# Simon_Says_Jump_MAIN.net
KiCad netlist of a schematic drawn in EAGLE
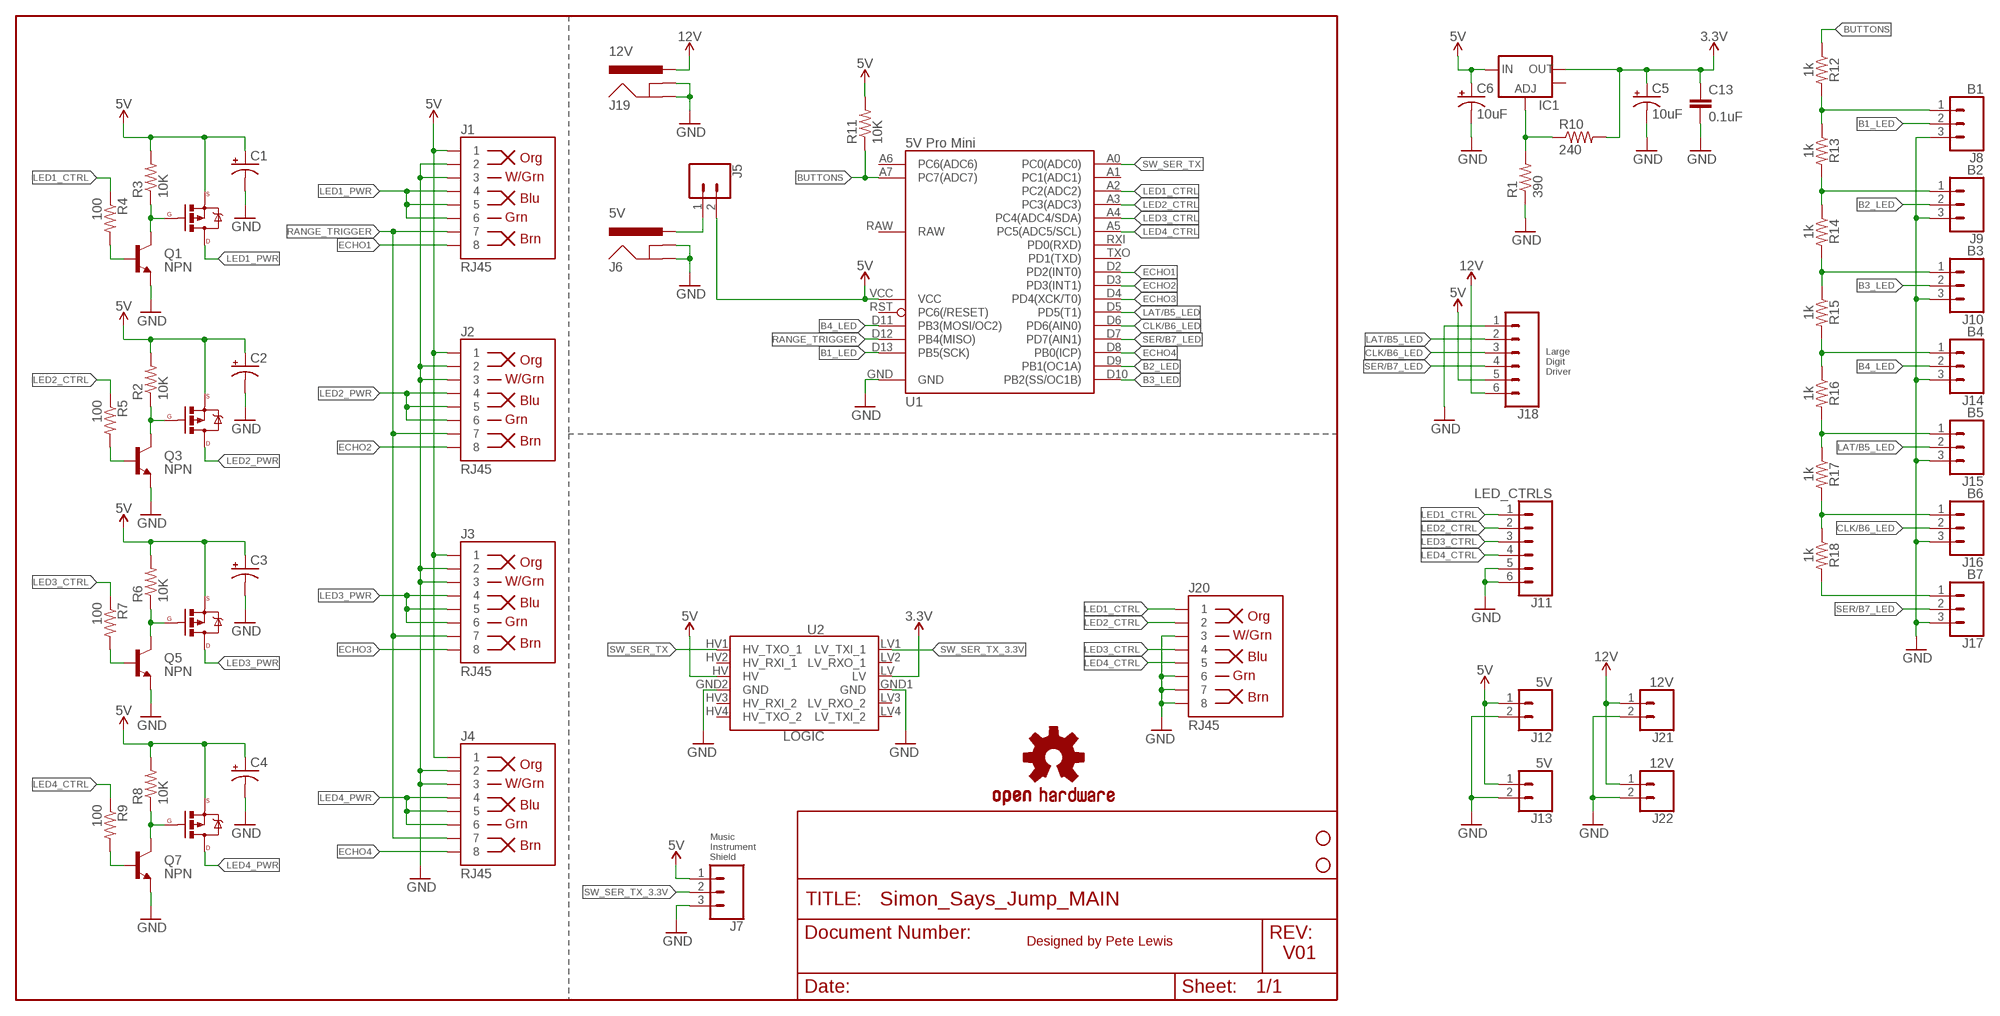
[diagram p0: schematic, sheet 1]

(export (version "E")
  (design (tool "Eeschema 10.0.6"))
  (components
    (comp (ref "C1")
      (value "CAP_POLCPOL-RADIAL-10UF-25V-KIT")
      (footprint "eagle-import:CPOL-RADIAL-10UF-25V-KIT")
      (libsource (lib "eagle-import") (part "CAP_POLCPOL-RADIAL-10UF-25V-KIT"))
    )
    (comp (ref "C2")
      (value "CAP_POLCPOL-RADIAL-10UF-25V-KIT")
      (footprint "eagle-import:CPOL-RADIAL-10UF-25V-KIT")
      (libsource (lib "eagle-import") (part "CAP_POLCPOL-RADIAL-10UF-25V-KIT"))
    )
    (comp (ref "C3")
      (value "CAP_POLCPOL-RADIAL-10UF-25V-KIT")
      (footprint "eagle-import:CPOL-RADIAL-10UF-25V-KIT")
      (libsource (lib "eagle-import") (part "CAP_POLCPOL-RADIAL-10UF-25V-KIT"))
    )
    (comp (ref "C4")
      (value "CAP_POLCPOL-RADIAL-10UF-25V-KIT")
      (footprint "eagle-import:CPOL-RADIAL-10UF-25V-KIT")
      (libsource (lib "eagle-import") (part "CAP_POLCPOL-RADIAL-10UF-25V-KIT"))
    )
    (comp (ref "C5")
      (value "10uF")
      (footprint "eagle-import:EIA3216")
      (libsource (lib "eagle-import") (part "CAP_POL1206"))
    )
    (comp (ref "C6")
      (value "10uF")
      (footprint "eagle-import:EIA3216")
      (libsource (lib "eagle-import") (part "CAP_POL1206"))
    )
    (comp (ref "C13")
      (value "0.1uF")
      (footprint "eagle-import:0603-CAP")
      (libsource (lib "eagle-import") (part "CAP0603-CAP"))
    )
    (comp (ref "IC1")
      (value "V_REG_LM1117SOT223")
      (footprint "eagle-import:SOT223")
      (libsource (lib "eagle-import") (part "V_REG_LM1117SOT223"))
    )
    (comp (ref "J1")
      (value "RJ45")
      (footprint "eagle-import:RJ45-8")
      (libsource (lib "eagle-import") (part "RJ45-8"))
    )
    (comp (ref "J2")
      (value "RJ45")
      (footprint "eagle-import:RJ45-8")
      (libsource (lib "eagle-import") (part "RJ45-8"))
    )
    (comp (ref "J3")
      (value "RJ45")
      (footprint "eagle-import:RJ45-8")
      (libsource (lib "eagle-import") (part "RJ45-8"))
    )
    (comp (ref "J4")
      (value "RJ45")
      (footprint "eagle-import:RJ45-8")
      (libsource (lib "eagle-import") (part "RJ45-8"))
    )
    (comp (ref "J5")
      (value "CONN_02PTH3")
      (footprint "eagle-import:1X02_LONGPADS")
      (libsource (lib "eagle-import") (part "CONN_02PTH3"))
    )
    (comp (ref "J6")
      (value "5V")
      (footprint "eagle-import:POWER_JACK_PTH_LOCK")
      (libsource (lib "eagle-import") (part "POWER_JACKPTH_LOCK"))
    )
    (comp (ref "J7")
      (value "CONN_03LONGPADS")
      (footprint "eagle-import:1X03_LONGPADS")
      (libsource (lib "eagle-import") (part "CONN_03LONGPADS"))
    )
    (comp (ref "J8")
      (value "B1")
      (footprint "eagle-import:1X03_LONGPADS")
      (libsource (lib "eagle-import") (part "CONN_03LONGPADS"))
    )
    (comp (ref "J9")
      (value "B2")
      (footprint "eagle-import:1X03_LONGPADS")
      (libsource (lib "eagle-import") (part "CONN_03LONGPADS"))
    )
    (comp (ref "J10")
      (value "B3")
      (footprint "eagle-import:1X03_LONGPADS")
      (libsource (lib "eagle-import") (part "CONN_03LONGPADS"))
    )
    (comp (ref "J11")
      (value "LED_CTRLS")
      (footprint "eagle-import:1X06_LONGPADS")
      (libsource (lib "eagle-import") (part "CONN_06LONGPADS"))
    )
    (comp (ref "J12")
      (value "5V")
      (footprint "eagle-import:1X02_LONGPADS")
      (libsource (lib "eagle-import") (part "CONN_02PTH3"))
    )
    (comp (ref "J13")
      (value "5V")
      (footprint "eagle-import:1X02_LONGPADS")
      (libsource (lib "eagle-import") (part "CONN_02PTH3"))
    )
    (comp (ref "J14")
      (value "B4")
      (footprint "eagle-import:1X03_LONGPADS")
      (libsource (lib "eagle-import") (part "CONN_03LONGPADS"))
    )
    (comp (ref "J15")
      (value "B5")
      (footprint "eagle-import:1X03_LONGPADS")
      (libsource (lib "eagle-import") (part "CONN_03LONGPADS"))
    )
    (comp (ref "J16")
      (value "B6")
      (footprint "eagle-import:1X03_LONGPADS")
      (libsource (lib "eagle-import") (part "CONN_03LONGPADS"))
    )
    (comp (ref "J17")
      (value "B7")
      (footprint "eagle-import:1X03_LONGPADS")
      (libsource (lib "eagle-import") (part "CONN_03LONGPADS"))
    )
    (comp (ref "J18")
      (value "CONN_06LONGPADS")
      (footprint "eagle-import:1X06_LONGPADS")
      (libsource (lib "eagle-import") (part "CONN_06LONGPADS"))
    )
    (comp (ref "J19")
      (value "12V")
      (footprint "eagle-import:POWER_JACK_PTH_LOCK")
      (libsource (lib "eagle-import") (part "POWER_JACKPTH_LOCK"))
    )
    (comp (ref "J20")
      (value "RJ45")
      (footprint "eagle-import:RJ45-8")
      (libsource (lib "eagle-import") (part "RJ45-8"))
    )
    (comp (ref "J21")
      (value "12V")
      (footprint "eagle-import:1X02_LONGPADS")
      (libsource (lib "eagle-import") (part "CONN_02PTH3"))
    )
    (comp (ref "J22")
      (value "12V")
      (footprint "eagle-import:1X02_LONGPADS")
      (libsource (lib "eagle-import") (part "CONN_02PTH3"))
    )
    (comp (ref "JP1")
      (value "STAND-OFFTIGHTER")
      (footprint "eagle-import:STAND-OFF-TIGHTER")
      (libsource (lib "eagle-import") (part "STAND-OFFTIGHTER"))
    )
    (comp (ref "JP7")
      (value "STAND-OFFTIGHTER")
      (footprint "eagle-import:STAND-OFF-TIGHTER")
      (libsource (lib "eagle-import") (part "STAND-OFFTIGHTER"))
    )
    (comp (ref "LOGO1")
      (value "OSHW-LOGOL")
      (footprint "eagle-import:OSHW-LOGO-L")
      (libsource (lib "eagle-import") (part "OSHW-LOGOL"))
    )
    (comp (ref "Q1")
      (value "NPN")
      (footprint "eagle-import:SOT23")
      (libsource (lib "eagle-import") (part "TRANSISTOR_NPNSOT23"))
    )
    (comp (ref "Q2")
      (value "P-Channel MOSFET")
      (footprint "eagle-import:TO220V")
      (libsource (lib "eagle-import") (part "MOSFET-PCHANNELPTH"))
    )
    (comp (ref "Q3")
      (value "NPN")
      (footprint "eagle-import:SOT23")
      (libsource (lib "eagle-import") (part "TRANSISTOR_NPNSOT23"))
    )
    (comp (ref "Q4")
      (value "P-Channel MOSFET")
      (footprint "eagle-import:TO220V")
      (libsource (lib "eagle-import") (part "MOSFET-PCHANNELPTH"))
    )
    (comp (ref "Q5")
      (value "NPN")
      (footprint "eagle-import:SOT23")
      (libsource (lib "eagle-import") (part "TRANSISTOR_NPNSOT23"))
    )
    (comp (ref "Q6")
      (value "P-Channel MOSFET")
      (footprint "eagle-import:TO220V")
      (libsource (lib "eagle-import") (part "MOSFET-PCHANNELPTH"))
    )
    (comp (ref "Q7")
      (value "NPN")
      (footprint "eagle-import:SOT23")
      (libsource (lib "eagle-import") (part "TRANSISTOR_NPNSOT23"))
    )
    (comp (ref "Q8")
      (value "P-Channel MOSFET")
      (footprint "eagle-import:TO220V")
      (libsource (lib "eagle-import") (part "MOSFET-PCHANNELPTH"))
    )
    (comp (ref "R1")
      (value "390")
      (footprint "eagle-import:0603-RES")
      (libsource (lib "eagle-import") (part "RESISTOR0603-RES"))
    )
    (comp (ref "R2")
      (value "10K")
      (footprint "eagle-import:0603-RES")
      (libsource (lib "eagle-import") (part "RESISTOR0603-RES"))
    )
    (comp (ref "R3")
      (value "10K")
      (footprint "eagle-import:0603-RES")
      (libsource (lib "eagle-import") (part "RESISTOR0603-RES"))
    )
    (comp (ref "R4")
      (value "100")
      (footprint "eagle-import:0603-RES")
      (libsource (lib "eagle-import") (part "RESISTOR0603-RES"))
    )
    (comp (ref "R5")
      (value "100")
      (footprint "eagle-import:0603-RES")
      (libsource (lib "eagle-import") (part "RESISTOR0603-RES"))
    )
    (comp (ref "R6")
      (value "10K")
      (footprint "eagle-import:0603-RES")
      (libsource (lib "eagle-import") (part "RESISTOR0603-RES"))
    )
    (comp (ref "R7")
      (value "100")
      (footprint "eagle-import:0603-RES")
      (libsource (lib "eagle-import") (part "RESISTOR0603-RES"))
    )
    (comp (ref "R8")
      (value "10K")
      (footprint "eagle-import:0603-RES")
      (libsource (lib "eagle-import") (part "RESISTOR0603-RES"))
    )
    (comp (ref "R9")
      (value "100")
      (footprint "eagle-import:0603-RES")
      (libsource (lib "eagle-import") (part "RESISTOR0603-RES"))
    )
    (comp (ref "R10")
      (value "240")
      (footprint "eagle-import:0603-RES")
      (libsource (lib "eagle-import") (part "RESISTOR0603-RES"))
    )
    (comp (ref "R11")
      (value "10K")
      (footprint "eagle-import:0603-RES")
      (libsource (lib "eagle-import") (part "RESISTOR0603-RES"))
    )
    (comp (ref "R12")
      (value "1k")
      (footprint "eagle-import:0603")
      (libsource (lib "eagle-import") (part "1KOHM-0603-1/10W-1%"))
    )
    (comp (ref "R13")
      (value "1k")
      (footprint "eagle-import:0603")
      (libsource (lib "eagle-import") (part "1KOHM-0603-1/10W-1%"))
    )
    (comp (ref "R14")
      (value "1k")
      (footprint "eagle-import:0603")
      (libsource (lib "eagle-import") (part "1KOHM-0603-1/10W-1%"))
    )
    (comp (ref "R15")
      (value "1k")
      (footprint "eagle-import:0603")
      (libsource (lib "eagle-import") (part "1KOHM-0603-1/10W-1%"))
    )
    (comp (ref "R16")
      (value "1k")
      (footprint "eagle-import:0603")
      (libsource (lib "eagle-import") (part "1KOHM-0603-1/10W-1%"))
    )
    (comp (ref "R17")
      (value "1k")
      (footprint "eagle-import:0603")
      (libsource (lib "eagle-import") (part "1KOHM-0603-1/10W-1%"))
    )
    (comp (ref "R18")
      (value "1k")
      (footprint "eagle-import:0603")
      (libsource (lib "eagle-import") (part "1KOHM-0603-1/10W-1%"))
    )
    (comp (ref "U1")
      (value "5V Pro Mini")
      (footprint "eagle-import:ARDUINO_PRO_MINI-V13_DIP")
      (libsource (lib "eagle-import") (part "ARDUINO_PRO_MINI-V13-DIP"))
    )
    (comp (ref "U2")
      (value "LOGIC")
      (footprint "eagle-import:SPARKFUN_LOGIC_LEVEL_CONVERTER")
      (libsource (lib "eagle-import") (part "SPARKFUN_LOGIC_LEVEL_CONVERTER"))
    )
  )
  (nets
    (net (code "1") (name "3.3V") (class "Default")
      (node (ref "C13") (pin "1") (pinfunction "1_1") (pintype "passive"))
      (node (ref "C5") (pin "A") (pinfunction "+_A") (pintype "passive"))
      (node (ref "IC1") (pin "2") (pinfunction "OUT_2") (pintype "output"))
      (node (ref "R10") (pin "2") (pinfunction "2_2") (pintype "passive"))
      (node (ref "U2") (pin "LV") (pinfunction "LV_LV") (pintype "power_in"))
    )
    (net (code "2") (name "5V") (class "Default")
      (node (ref "C1") (pin "1") (pinfunction "+_1") (pintype "passive"))
      (node (ref "C2") (pin "1") (pinfunction "+_1") (pintype "passive"))
      (node (ref "C3") (pin "1") (pinfunction "+_1") (pintype "passive"))
      (node (ref "C4") (pin "1") (pinfunction "+_1") (pintype "passive"))
      (node (ref "C6") (pin "A") (pinfunction "+_A") (pintype "passive"))
      (node (ref "IC1") (pin "3") (pinfunction "IN_3") (pintype "input"))
      (node (ref "J1") (pin "1") (pinfunction "1_1") (pintype "bidirectional"))
      (node (ref "J12") (pin "1") (pinfunction "1_1") (pintype "passive"))
      (node (ref "J13") (pin "1") (pinfunction "1_1") (pintype "passive"))
      (node (ref "J18") (pin "5") (pinfunction "5_5") (pintype "passive"))
      (node (ref "J2") (pin "1") (pinfunction "1_1") (pintype "bidirectional"))
      (node (ref "J3") (pin "1") (pinfunction "1_1") (pintype "bidirectional"))
      (node (ref "J4") (pin "1") (pinfunction "1_1") (pintype "bidirectional"))
      (node (ref "J5") (pin "2") (pinfunction "2_2") (pintype "passive"))
      (node (ref "J7") (pin "1") (pinfunction "1_1") (pintype "passive"))
      (node (ref "Q2") (pin "3") (pinfunction "S_3") (pintype "passive"))
      (node (ref "Q4") (pin "3") (pinfunction "S_3") (pintype "passive"))
      (node (ref "Q6") (pin "3") (pinfunction "S_3") (pintype "passive"))
      (node (ref "Q8") (pin "3") (pinfunction "S_3") (pintype "passive"))
      (node (ref "R11") (pin "2") (pinfunction "2_2") (pintype "passive"))
      (node (ref "R2") (pin "2") (pinfunction "2_2") (pintype "passive"))
      (node (ref "R3") (pin "2") (pinfunction "2_2") (pintype "passive"))
      (node (ref "R6") (pin "2") (pinfunction "2_2") (pintype "passive"))
      (node (ref "R8") (pin "2") (pinfunction "2_2") (pintype "passive"))
      (node (ref "U1") (pin "VCC") (pinfunction "VCC_VCC") (pintype "bidirectional"))
      (node (ref "U2") (pin "HV") (pinfunction "HV_HV") (pintype "power_in"))
    )
    (net (code "3") (name "12V") (class "Default")
      (node (ref "J18") (pin "6") (pinfunction "6_6") (pintype "passive"))
      (node (ref "J19") (pin "PWR") (pinfunction "PWR_PWR") (pintype "bidirectional"))
      (node (ref "J21") (pin "1") (pinfunction "1_1") (pintype "passive"))
      (node (ref "J22") (pin "1") (pinfunction "1_1") (pintype "passive"))
    )
    (net (code "4") (name "B1_LED") (class "Default")
      (node (ref "J8") (pin "2") (pinfunction "2_2") (pintype "passive"))
      (node (ref "U1") (pin "D13") (pinfunction "PB5(SCK)_D13") (pintype "bidirectional"))
    )
    (net (code "5") (name "B2_LED") (class "Default")
      (node (ref "J9") (pin "2") (pinfunction "2_2") (pintype "passive"))
      (node (ref "U1") (pin "D9") (pinfunction "PB1(OC1A)_D9") (pintype "bidirectional"))
    )
    (net (code "6") (name "B3_LED") (class "Default")
      (node (ref "J10") (pin "2") (pinfunction "2_2") (pintype "passive"))
      (node (ref "U1") (pin "D10") (pinfunction "PB2(SS/OC1B)_D10") (pintype "bidirectional"))
    )
    (net (code "7") (name "B4_LED") (class "Default")
      (node (ref "J14") (pin "2") (pinfunction "2_2") (pintype "passive"))
      (node (ref "U1") (pin "D11") (pinfunction "PB3(MOSI/OC2)_D11") (pintype "bidirectional"))
    )
    (net (code "8") (name "BUTTONS") (class "Default")
      (node (ref "R11") (pin "1") (pinfunction "1_1") (pintype "passive"))
      (node (ref "R12") (pin "1") (pinfunction "1_1") (pintype "passive"))
      (node (ref "U1") (pin "A7") (pinfunction "PC7(ADC7)_A7") (pintype "bidirectional"))
    )
    (net (code "9") (name "CLK{slash}B6_LED") (class "Default")
      (node (ref "J16") (pin "2") (pinfunction "2_2") (pintype "passive"))
      (node (ref "J18") (pin "3") (pinfunction "3_3") (pintype "passive"))
      (node (ref "U1") (pin "D6") (pinfunction "PD6(AIN0)_D6") (pintype "bidirectional"))
    )
    (net (code "10") (name "ECHO1") (class "Default")
      (node (ref "J1") (pin "8") (pinfunction "8_8") (pintype "bidirectional"))
      (node (ref "U1") (pin "D2") (pinfunction "PD2(INT0)_D2") (pintype "bidirectional"))
    )
    (net (code "11") (name "ECHO2") (class "Default")
      (node (ref "J2") (pin "8") (pinfunction "8_8") (pintype "bidirectional"))
      (node (ref "U1") (pin "D3") (pinfunction "PD3(INT1)_D3") (pintype "bidirectional"))
    )
    (net (code "12") (name "ECHO3") (class "Default")
      (node (ref "J3") (pin "8") (pinfunction "8_8") (pintype "bidirectional"))
      (node (ref "U1") (pin "D4") (pinfunction "PD4(XCK/T0)_D4") (pintype "bidirectional"))
    )
    (net (code "13") (name "ECHO4") (class "Default")
      (node (ref "J4") (pin "8") (pinfunction "8_8") (pintype "bidirectional"))
      (node (ref "U1") (pin "D8") (pinfunction "PB0(ICP)_D8") (pintype "bidirectional"))
    )
    (net (code "14") (name "GND") (class "Default")
      (node (ref "C1") (pin "2") (pinfunction "-_2") (pintype "passive"))
      (node (ref "C13") (pin "2") (pinfunction "2_2") (pintype "passive"))
      (node (ref "C2") (pin "2") (pinfunction "-_2") (pintype "passive"))
      (node (ref "C3") (pin "2") (pinfunction "-_2") (pintype "passive"))
      (node (ref "C4") (pin "2") (pinfunction "-_2") (pintype "passive"))
      (node (ref "C5") (pin "C") (pinfunction "-_C") (pintype "passive"))
      (node (ref "C6") (pin "C") (pinfunction "-_C") (pintype "passive"))
      (node (ref "J1") (pin "2") (pinfunction "2_2") (pintype "bidirectional"))
      (node (ref "J1") (pin "3") (pinfunction "3_3") (pintype "bidirectional"))
      (node (ref "J10") (pin "3") (pinfunction "3_3") (pintype "passive"))
      (node (ref "J11") (pin "5") (pinfunction "5_5") (pintype "passive"))
      (node (ref "J11") (pin "6") (pinfunction "6_6") (pintype "passive"))
      (node (ref "J12") (pin "2") (pinfunction "2_2") (pintype "passive"))
      (node (ref "J13") (pin "2") (pinfunction "2_2") (pintype "passive"))
      (node (ref "J14") (pin "3") (pinfunction "3_3") (pintype "passive"))
      (node (ref "J15") (pin "3") (pinfunction "3_3") (pintype "passive"))
      (node (ref "J16") (pin "3") (pinfunction "3_3") (pintype "passive"))
      (node (ref "J17") (pin "3") (pinfunction "3_3") (pintype "passive"))
      (node (ref "J18") (pin "1") (pinfunction "1_1") (pintype "passive"))
      (node (ref "J19") (pin "GND") (pinfunction "GND_GND") (pintype "bidirectional"))
      (node (ref "J19") (pin "GNDBREAK") (pinfunction "GNDBREAK_GNDBREAK") (pintype "bidirectional"))
      (node (ref "J2") (pin "2") (pinfunction "2_2") (pintype "bidirectional"))
      (node (ref "J2") (pin "3") (pinfunction "3_3") (pintype "bidirectional"))
      (node (ref "J20") (pin "3") (pinfunction "3_3") (pintype "bidirectional"))
      (node (ref "J20") (pin "6") (pinfunction "6_6") (pintype "bidirectional"))
      (node (ref "J20") (pin "7") (pinfunction "7_7") (pintype "bidirectional"))
      (node (ref "J20") (pin "8") (pinfunction "8_8") (pintype "bidirectional"))
      (node (ref "J21") (pin "2") (pinfunction "2_2") (pintype "passive"))
      (node (ref "J22") (pin "2") (pinfunction "2_2") (pintype "passive"))
      (node (ref "J3") (pin "2") (pinfunction "2_2") (pintype "bidirectional"))
      (node (ref "J3") (pin "3") (pinfunction "3_3") (pintype "bidirectional"))
      (node (ref "J4") (pin "2") (pinfunction "2_2") (pintype "bidirectional"))
      (node (ref "J4") (pin "3") (pinfunction "3_3") (pintype "bidirectional"))
      (node (ref "J6") (pin "GND") (pinfunction "GND_GND") (pintype "bidirectional"))
      (node (ref "J6") (pin "GNDBREAK") (pinfunction "GNDBREAK_GNDBREAK") (pintype "bidirectional"))
      (node (ref "J7") (pin "3") (pinfunction "3_3") (pintype "passive"))
      (node (ref "J8") (pin "3") (pinfunction "3_3") (pintype "passive"))
      (node (ref "J9") (pin "3") (pinfunction "3_3") (pintype "passive"))
      (node (ref "Q1") (pin "2") (pinfunction "E_2") (pintype "passive"))
      (node (ref "Q3") (pin "2") (pinfunction "E_2") (pintype "passive"))
      (node (ref "Q5") (pin "2") (pinfunction "E_2") (pintype "passive"))
      (node (ref "Q7") (pin "2") (pinfunction "E_2") (pintype "passive"))
      (node (ref "R1") (pin "1") (pinfunction "1_1") (pintype "passive"))
      (node (ref "U1") (pin "GND") (pinfunction "GND_GND") (pintype "bidirectional"))
      (node (ref "U2") (pin "GND1") (pinfunction "GND_GND1") (pintype "power_in"))
      (node (ref "U2") (pin "GND2") (pinfunction "GND_GND2") (pintype "power_in"))
    )
    (net (code "15") (name "LAT{slash}B5_LED") (class "Default")
      (node (ref "J15") (pin "2") (pinfunction "2_2") (pintype "passive"))
      (node (ref "J18") (pin "2") (pinfunction "2_2") (pintype "passive"))
      (node (ref "U1") (pin "D5") (pinfunction "PD5(T1)_D5") (pintype "bidirectional"))
    )
    (net (code "16") (name "LED1_CTRL") (class "Default")
      (node (ref "J11") (pin "1") (pinfunction "1_1") (pintype "passive"))
      (node (ref "J20") (pin "1") (pinfunction "1_1") (pintype "bidirectional"))
      (node (ref "R4") (pin "1") (pinfunction "1_1") (pintype "passive"))
      (node (ref "U1") (pin "A2") (pinfunction "PC2(ADC2)_A2") (pintype "bidirectional"))
    )
    (net (code "17") (name "LED1_PWR") (class "Default")
      (node (ref "J1") (pin "4") (pinfunction "4_4") (pintype "bidirectional"))
      (node (ref "J1") (pin "5") (pinfunction "5_5") (pintype "bidirectional"))
      (node (ref "J1") (pin "6") (pinfunction "6_6") (pintype "bidirectional"))
      (node (ref "Q2") (pin "2") (pinfunction "D_2") (pintype "passive"))
    )
    (net (code "18") (name "LED2_CTRL") (class "Default")
      (node (ref "J11") (pin "2") (pinfunction "2_2") (pintype "passive"))
      (node (ref "J20") (pin "2") (pinfunction "2_2") (pintype "bidirectional"))
      (node (ref "R5") (pin "1") (pinfunction "1_1") (pintype "passive"))
      (node (ref "U1") (pin "A3") (pinfunction "PC3(ADC3)_A3") (pintype "bidirectional"))
    )
    (net (code "19") (name "LED2_PWR") (class "Default")
      (node (ref "J2") (pin "4") (pinfunction "4_4") (pintype "bidirectional"))
      (node (ref "J2") (pin "5") (pinfunction "5_5") (pintype "bidirectional"))
      (node (ref "J2") (pin "6") (pinfunction "6_6") (pintype "bidirectional"))
      (node (ref "Q4") (pin "2") (pinfunction "D_2") (pintype "passive"))
    )
    (net (code "20") (name "LED3_CTRL") (class "Default")
      (node (ref "J11") (pin "3") (pinfunction "3_3") (pintype "passive"))
      (node (ref "J20") (pin "4") (pinfunction "4_4") (pintype "bidirectional"))
      (node (ref "R7") (pin "1") (pinfunction "1_1") (pintype "passive"))
      (node (ref "U1") (pin "A4") (pinfunction "PC4(ADC4/SDA)_A4") (pintype "bidirectional"))
    )
    (net (code "21") (name "LED3_PWR") (class "Default")
      (node (ref "J3") (pin "4") (pinfunction "4_4") (pintype "bidirectional"))
      (node (ref "J3") (pin "5") (pinfunction "5_5") (pintype "bidirectional"))
      (node (ref "J3") (pin "6") (pinfunction "6_6") (pintype "bidirectional"))
      (node (ref "Q6") (pin "2") (pinfunction "D_2") (pintype "passive"))
    )
    (net (code "22") (name "LED4_CTRL") (class "Default")
      (node (ref "J11") (pin "4") (pinfunction "4_4") (pintype "passive"))
      (node (ref "J20") (pin "5") (pinfunction "5_5") (pintype "bidirectional"))
      (node (ref "R9") (pin "1") (pinfunction "1_1") (pintype "passive"))
      (node (ref "U1") (pin "A5") (pinfunction "PC5(ADC5/SCL)_A5") (pintype "bidirectional"))
    )
    (net (code "23") (name "LED4_PWR") (class "Default")
      (node (ref "J4") (pin "4") (pinfunction "4_4") (pintype "bidirectional"))
      (node (ref "J4") (pin "5") (pinfunction "5_5") (pintype "bidirectional"))
      (node (ref "J4") (pin "6") (pinfunction "6_6") (pintype "bidirectional"))
      (node (ref "Q8") (pin "2") (pinfunction "D_2") (pintype "passive"))
    )
    (net (code "24") (name "Net-(IC1-ADJ)") (class "Default")
      (node (ref "IC1") (pin "1") (pinfunction "ADJ_1") (pintype "input"))
      (node (ref "R1") (pin "2") (pinfunction "2_2") (pintype "passive"))
      (node (ref "R10") (pin "1") (pinfunction "1_1") (pintype "passive"))
    )
    (net (code "25") (name "Net-(J5-Pad1)") (class "Default")
      (node (ref "J5") (pin "1") (pinfunction "1_1") (pintype "passive"))
      (node (ref "J6") (pin "PWR") (pinfunction "PWR_PWR") (pintype "bidirectional"))
    )
    (net (code "26") (name "Net-(J8-Pad1)") (class "Default")
      (node (ref "J8") (pin "1") (pinfunction "1_1") (pintype "passive"))
      (node (ref "R12") (pin "2") (pinfunction "2_2") (pintype "passive"))
      (node (ref "R13") (pin "1") (pinfunction "1_1") (pintype "passive"))
    )
    (net (code "27") (name "Net-(J9-Pad1)") (class "Default")
      (node (ref "J9") (pin "1") (pinfunction "1_1") (pintype "passive"))
      (node (ref "R13") (pin "2") (pinfunction "2_2") (pintype "passive"))
      (node (ref "R14") (pin "1") (pinfunction "1_1") (pintype "passive"))
    )
    (net (code "28") (name "Net-(J10-Pad1)") (class "Default")
      (node (ref "J10") (pin "1") (pinfunction "1_1") (pintype "passive"))
      (node (ref "R14") (pin "2") (pinfunction "2_2") (pintype "passive"))
      (node (ref "R15") (pin "1") (pinfunction "1_1") (pintype "passive"))
    )
    (net (code "29") (name "Net-(J14-Pad1)") (class "Default")
      (node (ref "J14") (pin "1") (pinfunction "1_1") (pintype "passive"))
      (node (ref "R15") (pin "2") (pinfunction "2_2") (pintype "passive"))
      (node (ref "R16") (pin "1") (pinfunction "1_1") (pintype "passive"))
    )
    (net (code "30") (name "Net-(J15-Pad1)") (class "Default")
      (node (ref "J15") (pin "1") (pinfunction "1_1") (pintype "passive"))
      (node (ref "R16") (pin "2") (pinfunction "2_2") (pintype "passive"))
      (node (ref "R17") (pin "1") (pinfunction "1_1") (pintype "passive"))
    )
    (net (code "31") (name "Net-(J16-Pad1)") (class "Default")
      (node (ref "J16") (pin "1") (pinfunction "1_1") (pintype "passive"))
      (node (ref "R17") (pin "2") (pinfunction "2_2") (pintype "passive"))
      (node (ref "R18") (pin "1") (pinfunction "1_1") (pintype "passive"))
    )
    (net (code "32") (name "Net-(J17-Pad1)") (class "Default")
      (node (ref "J17") (pin "1") (pinfunction "1_1") (pintype "passive"))
      (node (ref "R18") (pin "2") (pinfunction "2_2") (pintype "passive"))
    )
    (net (code "33") (name "Net-(Q1-B)") (class "Default")
      (node (ref "Q1") (pin "1") (pinfunction "B_1") (pintype "passive"))
      (node (ref "R4") (pin "2") (pinfunction "2_2") (pintype "passive"))
    )
    (net (code "34") (name "Net-(Q1-C)") (class "Default")
      (node (ref "Q1") (pin "3") (pinfunction "C_3") (pintype "passive"))
      (node (ref "Q2") (pin "1") (pinfunction "G_1") (pintype "passive"))
      (node (ref "R3") (pin "1") (pinfunction "1_1") (pintype "passive"))
    )
    (net (code "35") (name "Net-(Q3-B)") (class "Default")
      (node (ref "Q3") (pin "1") (pinfunction "B_1") (pintype "passive"))
      (node (ref "R5") (pin "2") (pinfunction "2_2") (pintype "passive"))
    )
    (net (code "36") (name "Net-(Q3-C)") (class "Default")
      (node (ref "Q3") (pin "3") (pinfunction "C_3") (pintype "passive"))
      (node (ref "Q4") (pin "1") (pinfunction "G_1") (pintype "passive"))
      (node (ref "R2") (pin "1") (pinfunction "1_1") (pintype "passive"))
    )
    (net (code "37") (name "Net-(Q5-B)") (class "Default")
      (node (ref "Q5") (pin "1") (pinfunction "B_1") (pintype "passive"))
      (node (ref "R7") (pin "2") (pinfunction "2_2") (pintype "passive"))
    )
    (net (code "38") (name "Net-(Q5-C)") (class "Default")
      (node (ref "Q5") (pin "3") (pinfunction "C_3") (pintype "passive"))
      (node (ref "Q6") (pin "1") (pinfunction "G_1") (pintype "passive"))
      (node (ref "R6") (pin "1") (pinfunction "1_1") (pintype "passive"))
    )
    (net (code "39") (name "Net-(Q7-B)") (class "Default")
      (node (ref "Q7") (pin "1") (pinfunction "B_1") (pintype "passive"))
      (node (ref "R9") (pin "2") (pinfunction "2_2") (pintype "passive"))
    )
    (net (code "40") (name "Net-(Q7-C)") (class "Default")
      (node (ref "Q7") (pin "3") (pinfunction "C_3") (pintype "passive"))
      (node (ref "Q8") (pin "1") (pinfunction "G_1") (pintype "passive"))
      (node (ref "R8") (pin "1") (pinfunction "1_1") (pintype "passive"))
    )
    (net (code "41") (name "RANGE_TRIGGER") (class "Default")
      (node (ref "J1") (pin "7") (pinfunction "7_7") (pintype "bidirectional"))
      (node (ref "J2") (pin "7") (pinfunction "7_7") (pintype "bidirectional"))
      (node (ref "J3") (pin "7") (pinfunction "7_7") (pintype "bidirectional"))
      (node (ref "J4") (pin "7") (pinfunction "7_7") (pintype "bidirectional"))
      (node (ref "U1") (pin "D12") (pinfunction "PB4(MISO)_D12") (pintype "bidirectional"))
    )
    (net (code "42") (name "SER{slash}B7_LED") (class "Default")
      (node (ref "J17") (pin "2") (pinfunction "2_2") (pintype "passive"))
      (node (ref "J18") (pin "4") (pinfunction "4_4") (pintype "passive"))
      (node (ref "U1") (pin "D7") (pinfunction "PD7(AIN1)_D7") (pintype "bidirectional"))
    )
    (net (code "43") (name "SW_SER_TX") (class "Default")
      (node (ref "U1") (pin "A0") (pinfunction "PC0(ADC0)_A0") (pintype "bidirectional"))
      (node (ref "U2") (pin "HV1") (pinfunction "HV_TXO_1_HV1") (pintype "bidirectional"))
    )
    (net (code "44") (name "SW_SER_TX_3.3V") (class "Default")
      (node (ref "J7") (pin "2") (pinfunction "2_2") (pintype "passive"))
      (node (ref "U2") (pin "LV1") (pinfunction "LV_TXI_1_LV1") (pintype "bidirectional"))
    )
    (net (code "45") (name "unconnected-(IC1-OUT-Pad4)") (class "Default")
      (node (ref "IC1") (pin "4") (pinfunction "OUT_4") (pintype "output"))
    )
    (net (code "46") (name "unconnected-(U1-PC1(ADC1)-PadA1)") (class "Default")
      (node (ref "U1") (pin "A1") (pinfunction "PC1(ADC1)_A1") (pintype "bidirectional"))
    )
    (net (code "47") (name "unconnected-(U1-PC6(ADC6)-PadA6)") (class "Default")
      (node (ref "U1") (pin "A6") (pinfunction "PC6(ADC6)_A6") (pintype "bidirectional"))
    )
    (net (code "48") (name "unconnected-(U1-PC6({slash}RESET)-PadRST)") (class "Default")
      (node (ref "U1") (pin "RST") (pinfunction "PC6(/RESET)_RST") (pintype "bidirectional"))
    )
    (net (code "49") (name "unconnected-(U1-PD0(RXD)-PadRXI)") (class "Default")
      (node (ref "U1") (pin "RXI") (pinfunction "PD0(RXD)_RXI") (pintype "bidirectional"))
    )
    (net (code "50") (name "unconnected-(U1-PD1(TXD)-PadTXO)") (class "Default")
      (node (ref "U1") (pin "TXO") (pinfunction "PD1(TXD)_TXO") (pintype "bidirectional"))
    )
    (net (code "51") (name "unconnected-(U1-PadRAW)") (class "Default")
      (node (ref "U1") (pin "RAW") (pinfunction "RAW_RAW") (pintype "bidirectional"))
    )
    (net (code "52") (name "unconnected-(U2-HV_RXI_1-PadHV2)") (class "Default")
      (node (ref "U2") (pin "HV2") (pinfunction "HV_RXI_1_HV2") (pintype "bidirectional"))
    )
    (net (code "53") (name "unconnected-(U2-HV_RXI_2-PadHV3)") (class "Default")
      (node (ref "U2") (pin "HV3") (pinfunction "HV_RXI_2_HV3") (pintype "bidirectional"))
    )
    (net (code "54") (name "unconnected-(U2-HV_TXO_2-PadHV4)") (class "Default")
      (node (ref "U2") (pin "HV4") (pinfunction "HV_TXO_2_HV4") (pintype "bidirectional"))
    )
    (net (code "55") (name "unconnected-(U2-LV_RXO_1-PadLV2)") (class "Default")
      (node (ref "U2") (pin "LV2") (pinfunction "LV_RXO_1_LV2") (pintype "bidirectional"))
    )
    (net (code "56") (name "unconnected-(U2-LV_RXO_2-PadLV3)") (class "Default")
      (node (ref "U2") (pin "LV3") (pinfunction "LV_RXO_2_LV3") (pintype "bidirectional"))
    )
    (net (code "57") (name "unconnected-(U2-LV_TXI_2-PadLV4)") (class "Default")
      (node (ref "U2") (pin "LV4") (pinfunction "LV_TXI_2_LV4") (pintype "bidirectional"))
    )
  )
)
